# CPU.net
KiCad netlist of a schematic drawn in Altium Designer
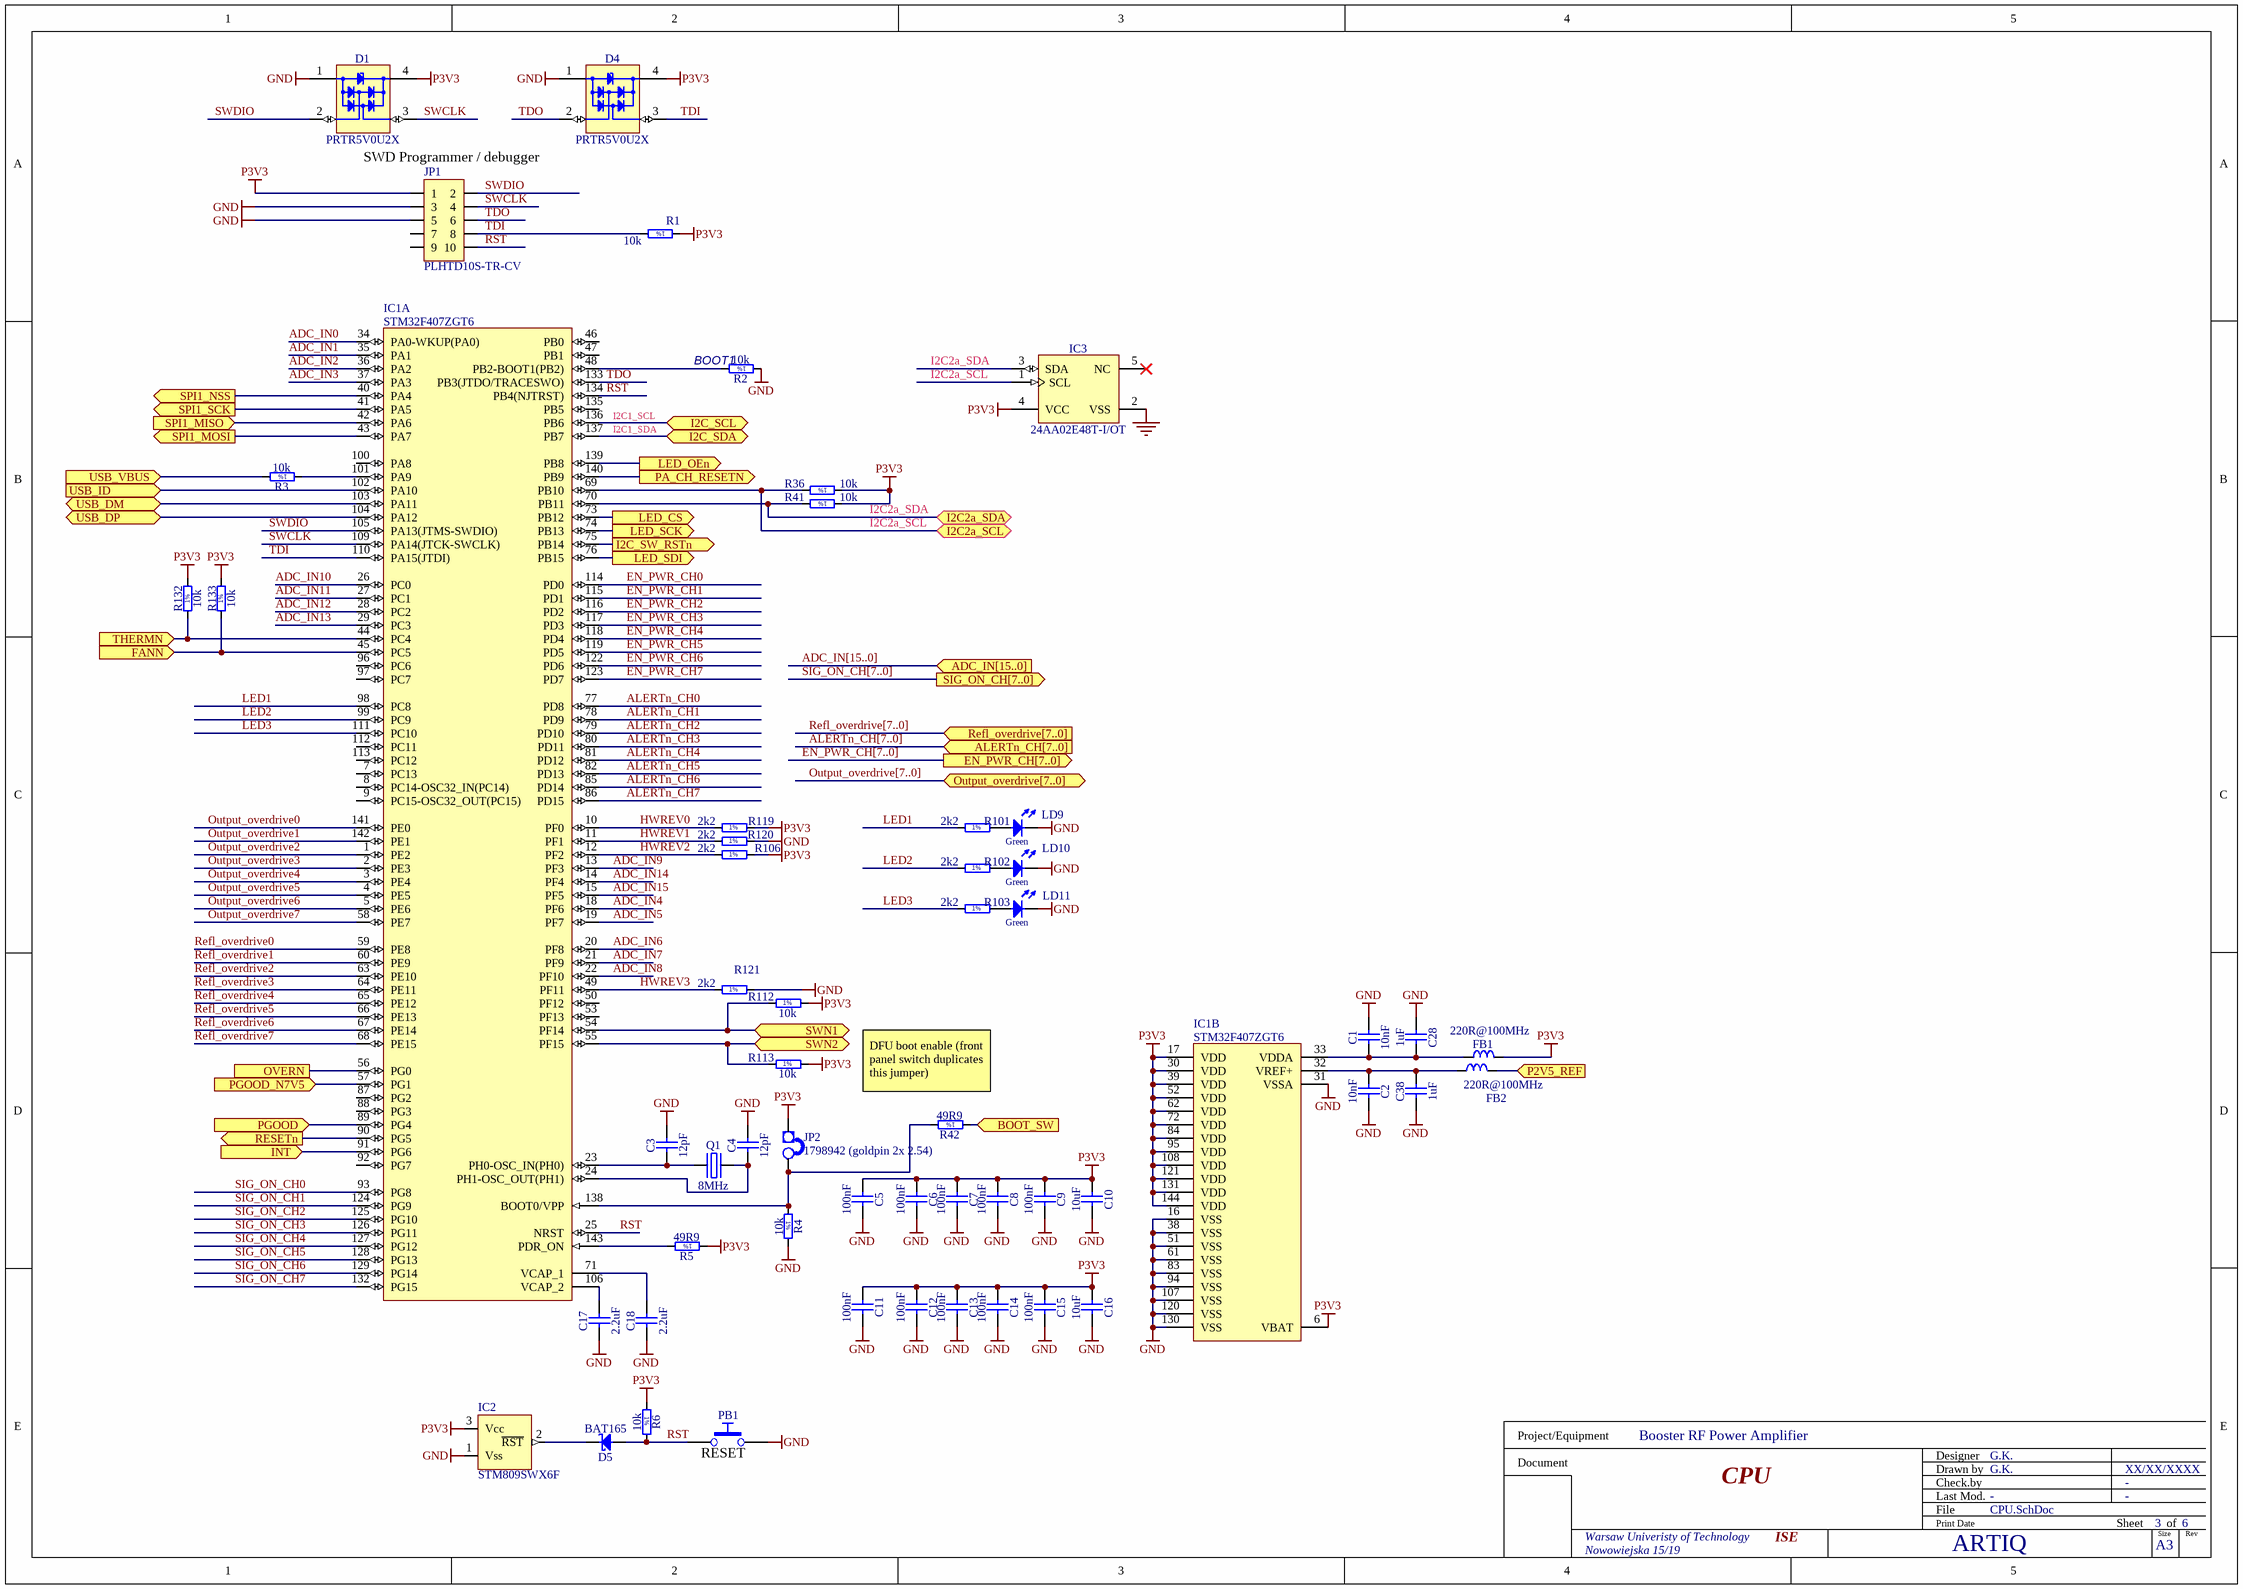
[diagram p0: CPU.SchDoc]

(export (version "E")
  (design (tool "Eeschema 10.0.6"))
  (components
    (comp (ref "C1")
      (value "10nF")
      (footprint "CAPC1005X55N")
      (description "Non-polarised capacitor")
      (fields
        (field (name "PART NUMBER") "CC0402_10NF_16V_10%_X7R")
        (field (name "VOLTAGE") "16V")
        (field (name "AUTHOR") "CERN DEM JLC")
      )
      (libsource (lib "Capacitors") (part "Capacitor - non polarized"))
    )
    (comp (ref "C2")
      (value "10nF")
      (footprint "CAPC1005X55N")
      (description "Non-polarised capacitor")
      (fields
        (field (name "PART NUMBER") "CC0402_10NF_16V_10%_X7R")
        (field (name "VOLTAGE") "16V")
        (field (name "AUTHOR") "CERN DEM JLC")
      )
      (libsource (lib "Capacitors") (part "Capacitor - non polarized"))
    )
    (comp (ref "C3")
      (value "12pF")
      (footprint "CAPC1005X55N")
      (description "Non-polarised capacitor")
      (fields
        (field (name "PART NUMBER") "CC0402_12PF_50V_5%_C0G")
        (field (name "VOLTAGE") "50V")
        (field (name "AUTHOR") "CERN DEM JLC")
      )
      (libsource (lib "Capacitors") (part "Capacitor - non polarized"))
    )
    (comp (ref "C4")
      (value "12pF")
      (footprint "CAPC1005X55N")
      (description "Non-polarised capacitor")
      (fields
        (field (name "PART NUMBER") "CC0402_12PF_50V_5%_C0G")
        (field (name "VOLTAGE") "50V")
        (field (name "AUTHOR") "CERN DEM JLC")
      )
      (libsource (lib "Capacitors") (part "Capacitor - non polarized"))
    )
    (comp (ref "C5")
      (value "100nF")
      (footprint "CAPC1005X55N")
      (description "Non-polarised capacitor")
      (fields
        (field (name "PART NUMBER") "CC0402_100NF_16V_10%_X7R")
        (field (name "VOLTAGE") "16V")
        (field (name "AUTHOR") "CERN DEM JLC")
      )
      (libsource (lib "Capacitors") (part "Capacitor - non polarized"))
    )
    (comp (ref "C6")
      (value "100nF")
      (footprint "CAPC1005X55N")
      (description "Non-polarised capacitor")
      (fields
        (field (name "PART NUMBER") "CC0402_100NF_16V_10%_X7R")
        (field (name "VOLTAGE") "16V")
        (field (name "AUTHOR") "CERN DEM JLC")
      )
      (libsource (lib "Capacitors") (part "Capacitor - non polarized"))
    )
    (comp (ref "C7")
      (value "100nF")
      (footprint "CAPC1005X55N")
      (description "Non-polarised capacitor")
      (fields
        (field (name "PART NUMBER") "CC0402_100NF_16V_10%_X7R")
        (field (name "VOLTAGE") "16V")
        (field (name "AUTHOR") "CERN DEM JLC")
      )
      (libsource (lib "Capacitors") (part "Capacitor - non polarized"))
    )
    (comp (ref "C8")
      (value "100nF")
      (footprint "CAPC1005X55N")
      (description "Non-polarised capacitor")
      (fields
        (field (name "PART NUMBER") "CC0402_100NF_16V_10%_X7R")
        (field (name "VOLTAGE") "16V")
        (field (name "AUTHOR") "CERN DEM JLC")
      )
      (libsource (lib "Capacitors") (part "Capacitor - non polarized"))
    )
    (comp (ref "C9")
      (value "100nF")
      (footprint "CAPC1005X55N")
      (description "Non-polarised capacitor")
      (fields
        (field (name "PART NUMBER") "CC0402_100NF_16V_10%_X7R")
        (field (name "VOLTAGE") "16V")
        (field (name "AUTHOR") "CERN DEM JLC")
      )
      (libsource (lib "Capacitors") (part "Capacitor - non polarized"))
    )
    (comp (ref "C10")
      (value "10uF")
      (footprint "CAPC2012X135N")
      (description "Non-polarised capacitor")
      (fields
        (field (name "PART NUMBER") "CC0805_10UF_16V_10%_X5R")
        (field (name "VOLTAGE") "16V")
        (field (name "AUTHOR") "CERN DEM JLC")
      )
      (libsource (lib "Capacitors") (part "Capacitor - non polarized"))
    )
    (comp (ref "C11")
      (value "100nF")
      (footprint "CAPC1005X55N")
      (description "Non-polarised capacitor")
      (fields
        (field (name "PART NUMBER") "CC0402_100NF_16V_10%_X7R")
        (field (name "VOLTAGE") "16V")
        (field (name "AUTHOR") "CERN DEM JLC")
      )
      (libsource (lib "Capacitors") (part "Capacitor - non polarized"))
    )
    (comp (ref "C12")
      (value "100nF")
      (footprint "CAPC1005X55N")
      (description "Non-polarised capacitor")
      (fields
        (field (name "PART NUMBER") "CC0402_100NF_16V_10%_X7R")
        (field (name "VOLTAGE") "16V")
        (field (name "AUTHOR") "CERN DEM JLC")
      )
      (libsource (lib "Capacitors") (part "Capacitor - non polarized"))
    )
    (comp (ref "C13")
      (value "100nF")
      (footprint "CAPC1005X55N")
      (description "Non-polarised capacitor")
      (fields
        (field (name "PART NUMBER") "CC0402_100NF_16V_10%_X7R")
        (field (name "VOLTAGE") "16V")
        (field (name "AUTHOR") "CERN DEM JLC")
      )
      (libsource (lib "Capacitors") (part "Capacitor - non polarized"))
    )
    (comp (ref "C14")
      (value "100nF")
      (footprint "CAPC1005X55N")
      (description "Non-polarised capacitor")
      (fields
        (field (name "PART NUMBER") "CC0402_100NF_16V_10%_X7R")
        (field (name "VOLTAGE") "16V")
        (field (name "AUTHOR") "CERN DEM JLC")
      )
      (libsource (lib "Capacitors") (part "Capacitor - non polarized"))
    )
    (comp (ref "C15")
      (value "100nF")
      (footprint "CAPC1005X55N")
      (description "Non-polarised capacitor")
      (fields
        (field (name "PART NUMBER") "CC0402_100NF_16V_10%_X7R")
        (field (name "VOLTAGE") "16V")
        (field (name "AUTHOR") "CERN DEM JLC")
      )
      (libsource (lib "Capacitors") (part "Capacitor - non polarized"))
    )
    (comp (ref "C16")
      (value "10uF")
      (footprint "CAPC2012X135N")
      (description "Non-polarised capacitor")
      (fields
        (field (name "PART NUMBER") "CC0805_10UF_16V_10%_X5R")
        (field (name "VOLTAGE") "16V")
        (field (name "AUTHOR") "CERN DEM JLC")
      )
      (libsource (lib "Capacitors") (part "Capacitor - non polarized"))
    )
    (comp (ref "C17")
      (value "2.2uF")
      (footprint "CAPC1608X90N")
      (description "Non-polarised capacitor")
      (fields
        (field (name "PART NUMBER") "CC0603_2.2UF_10V_20%_X7R")
        (field (name "VOLTAGE") "10V")
        (field (name "AUTHOR") "CERN DEM JLC")
      )
      (libsource (lib "Capacitors") (part "Capacitor - non polarized"))
    )
    (comp (ref "C18")
      (value "2.2uF")
      (footprint "CAPC1608X90N")
      (description "Non-polarised capacitor")
      (fields
        (field (name "PART NUMBER") "CC0603_2.2UF_10V_20%_X7R")
        (field (name "VOLTAGE") "10V")
        (field (name "AUTHOR") "CERN DEM JLC")
      )
      (libsource (lib "Capacitors") (part "Capacitor - non polarized"))
    )
    (comp (ref "C28")
      (value "1uF")
      (footprint "CAPC2012X110N")
      (description "Non-polarised capacitor")
      (fields
        (field (name "PART NUMBER") "CC0805_1UF_50V_10%_X7R")
        (field (name "VOLTAGE") "50V")
        (field (name "AUTHOR") "CERN DEM JLC")
      )
      (libsource (lib "Capacitors") (part "Capacitor - non polarized"))
    )
    (comp (ref "C38")
      (value "1uF")
      (footprint "CAPC2012X110N")
      (description "Non-polarised capacitor")
      (fields
        (field (name "PART NUMBER") "CC0805_1UF_50V_10%_X7R")
        (field (name "VOLTAGE") "50V")
        (field (name "AUTHOR") "CERN DEM JLC")
      )
      (libsource (lib "Capacitors") (part "Capacitor - non polarized"))
    )
    (comp (ref "D1")
      (value "PRTR5V0U2X")
      (footprint "SOT190P230X110-4N")
      (description "Ultra Low Capacitance Double Rail-to-Rail ESD Protection Diode")
      (fields
        (field (name "VOLTAGE") "5.5V")
        (field (name "MANUFACTURER") "NXP SEMICONDUCTORS")
        (field (name "AUTHOR") "CERN DEM JLC")
      )
      (libsource (lib "ICs And Semiconductors") (part "PRTR5V0U2X"))
    )
    (comp (ref "D4")
      (value "PRTR5V0U2X")
      (footprint "SOT190P230X110-4N")
      (description "Ultra Low Capacitance Double Rail-to-Rail ESD Protection Diode")
      (fields
        (field (name "VOLTAGE") "5.5V")
        (field (name "MANUFACTURER") "NXP SEMICONDUCTORS")
        (field (name "AUTHOR") "CERN DEM JLC")
      )
      (libsource (lib "ICs And Semiconductors") (part "PRTR5V0U2X"))
    )
    (comp (ref "D5")
      (value "BAT165")
      (footprint "SOD2512X110N")
      (description "Schottky Diode")
      (fields
        (field (name "VOLTAGE") "40V")
        (field (name "POWER") "750mA")
        (field (name "AUTHOR") "CERN DEM JLC")
      )
      (libsource (lib "ICs And Semiconductors") (part "Diode Schottky"))
    )
    (comp (ref "FB1")
      (value "220R@100MHz")
      (footprint "INDC2012X105N")
      (description "Inductor")
      (fields
        (field (name "PART NUMBER") "IND0805_MURATA_BLM21PG221SN1D")
        (field (name "POWER") "2A")
        (field (name "AUTHOR") "CERN DEM JLC")
      )
      (libsource (lib "Inductors & Transformers") (part "Inductor"))
    )
    (comp (ref "FB2")
      (value "220R@100MHz")
      (footprint "INDC2012X105N")
      (description "Inductor")
      (fields
        (field (name "PART NUMBER") "IND0805_MURATA_BLM21PG221SN1D")
        (field (name "POWER") "2A")
        (field (name "AUTHOR") "CERN DEM JLC")
      )
      (libsource (lib "Inductors & Transformers") (part "Inductor"))
    )
    (comp (ref "IC1")
      (value "STM32F407ZGT6")
      (footprint "QFP50P2200X2200X160-144N")
      (fields (field (name "MANUFACTURER") "ST MICROELECTRONICS") (field (name "AUTHOR") "CERN DEM MR"))
      (libsource (lib "ICs And Semiconductors") (part "STM32F407ZGT6"))
    )
    (comp (ref "IC2")
      (value "STM809SWX6F")
      (footprint "SOT-23")
      (description "2.93V  Reset circuit")
      (libsource (lib "LIBRARY_SCH") (part "VMON_STM809"))
    )
    (comp (ref "IC3")
      (value "24AA02E48T-I/OT")
      (footprint "SOT95P280X145-5N")
      (description "1.7V-5.5V, 2K I2C Serial EEPROM With EUI-48 Node Identity")
      (fields (field (name "MANUFACTURER") "MICROCHIP TECHNOLOGY") (field (name "AUTHOR") "CERN DEM MR"))
      (libsource (lib "ICs And Semiconductors") (part "24AA02E48T-I/OT"))
    )
    (comp (ref "JP1")
      (value "PLHTD10S-TR-CV")
      (footprint "PLHTD10S-TR-CV")
      (description "1.27 mm dual row goldpin (Maritex)")
      (libsource (lib "LIBRARY_SCH") (part "CON_2x5 1.27 SMT Male"))
    )
    (comp (ref "JP2")
      (value "1798942 (goldpin 2x 2.54)")
      (footprint "jump")
      (description "Jumper")
      (fields (field (name "MANUFACTURER PART NUMBER") "BG030-02-A-0650-0300-N-G"))
      (libsource (lib "LIBRARY_SCH") (part "JUMPER"))
    )
    (comp (ref "LD9")
      (value "Green")
      (footprint "LED_OSRAM_LGL29K")
      (description "LED Green 1C 2A")
      (fields
        (field (name "PART NUMBER") "LED_OSRAM_LG L29K-G2J1-24-Z")
        (field (name "MANUFACTURER") "OSRAM")
        (field (name "AUTHOR") "CERN DEM JLC")
      )
      (libsource (lib "ICs And Semiconductors") (part "LED Green 1C 2A"))
    )
    (comp (ref "LD10")
      (value "Green")
      (footprint "LED_OSRAM_LGL29K")
      (description "LED Green 1C 2A")
      (fields
        (field (name "PART NUMBER") "LED_OSRAM_LG L29K-G2J1-24-Z")
        (field (name "MANUFACTURER") "OSRAM")
        (field (name "AUTHOR") "CERN DEM JLC")
      )
      (libsource (lib "ICs And Semiconductors") (part "LED Green 1C 2A"))
    )
    (comp (ref "LD11")
      (value "Green")
      (footprint "LED_OSRAM_LGL29K")
      (description "LED Green 1C 2A")
      (fields
        (field (name "PART NUMBER") "LED_OSRAM_LG L29K-G2J1-24-Z")
        (field (name "MANUFACTURER") "OSRAM")
        (field (name "AUTHOR") "CERN DEM JLC")
      )
      (libsource (lib "ICs And Semiconductors") (part "LED Green 1C 2A"))
    )
    (comp (ref "PB1")
      (value "Push Button")
      (footprint "PB_TYCO_FSMSM")
      (description "Push-Button Switch SPDT")
      (fields
        (field (name "PART NUMBER") "PB_TYCO_FSMSM")
        (field (name "MANUFACTURER") "TYCO ELECTRONICS")
        (field (name "AUTHOR") "CERN DEM JLC")
      )
      (libsource (lib "Eletro-mechanical") (part "PB SPST 1NO-2NO"))
    )
    (comp (ref "Q1")
      (value "8MHz")
      (footprint "XTAL_TXC_7A")
      (description "Quartz Crystal")
      (fields
        (field (name "PART NUMBER") "XTAL_8MHZ_TXC_7A-8.000MAAE-T")
        (field (name "MANUFACTURER") "TXC CORPORATION")
        (field (name "AUTHOR") "CERN DEM JLC")
      )
      (libsource (lib "ICs And Semiconductors") (part "Quartz Crystal"))
    )
    (comp (ref "R1")
      (value "10k")
      (footprint "RESC1005X40N")
      (description "Resistor - 1%")
      (fields
        (field (name "PART NUMBER") "R0402_10K_1%_0.0625W_100PPM")
        (field (name "POWER") "0.0625W")
        (field (name "AUTHOR") "CERN DEM JLC")
      )
      (libsource (lib "Resistors") (part "Resistor - 1%"))
    )
    (comp (ref "R2")
      (value "10k")
      (footprint "RESC1005X40N")
      (description "Resistor - 1%")
      (fields
        (field (name "PART NUMBER") "R0402_10K_1%_0.0625W_100PPM")
        (field (name "POWER") "0.0625W")
        (field (name "AUTHOR") "CERN DEM JLC")
      )
      (libsource (lib "Resistors") (part "Resistor - 1%"))
    )
    (comp (ref "R3")
      (value "10k")
      (footprint "RESC1005X40N")
      (description "Resistor - 1%")
      (fields
        (field (name "PART NUMBER") "R0402_10K_1%_0.0625W_100PPM")
        (field (name "POWER") "0.0625W")
        (field (name "AUTHOR") "CERN DEM JLC")
      )
      (libsource (lib "Resistors") (part "Resistor - 1%"))
    )
    (comp (ref "R4")
      (value "10k")
      (footprint "RESC1005X40N")
      (description "Resistor - 1%")
      (fields
        (field (name "PART NUMBER") "R0402_10K_1%_0.0625W_100PPM")
        (field (name "POWER") "0.0625W")
        (field (name "AUTHOR") "CERN DEM JLC")
      )
      (libsource (lib "Resistors") (part "Resistor - 1%"))
    )
    (comp (ref "R5")
      (value "49R9")
      (footprint "RESC1005X40N")
      (description "Resistor - 1%")
      (fields
        (field (name "PART NUMBER") "R0402_49R9_1%_0.0625W_100PPM")
        (field (name "POWER") "0.0625W")
        (field (name "AUTHOR") "CERN DEM JLC")
      )
      (libsource (lib "Resistors") (part "Resistor - 1%"))
    )
    (comp (ref "R6")
      (value "10k")
      (footprint "RESC1005X40N")
      (description "Resistor - 1%")
      (fields
        (field (name "PART NUMBER") "R0402_10K_1%_0.0625W_100PPM")
        (field (name "POWER") "0.0625W")
        (field (name "AUTHOR") "CERN DEM JLC")
      )
      (libsource (lib "Resistors") (part "Resistor - 1%"))
    )
    (comp (ref "R36")
      (value "10k")
      (footprint "RESC1005X40N")
      (description "Resistor - 1%")
      (fields
        (field (name "PART NUMBER") "R0402_10K_1%_0.0625W_100PPM")
        (field (name "POWER") "0.0625W")
        (field (name "AUTHOR") "CERN DEM JLC")
      )
      (libsource (lib "Resistors") (part "Resistor - 1%"))
    )
    (comp (ref "R41")
      (value "10k")
      (footprint "RESC1005X40N")
      (description "Resistor - 1%")
      (fields
        (field (name "PART NUMBER") "R0402_10K_1%_0.0625W_100PPM")
        (field (name "POWER") "0.0625W")
        (field (name "AUTHOR") "CERN DEM JLC")
      )
      (libsource (lib "Resistors") (part "Resistor - 1%"))
    )
    (comp (ref "R42")
      (value "49R9")
      (footprint "RESC1005X40N")
      (description "Resistor - 1%")
      (fields
        (field (name "PART NUMBER") "R0402_49R9_1%_0.0625W_100PPM")
        (field (name "POWER") "0.0625W")
        (field (name "AUTHOR") "CERN DEM JLC")
      )
      (libsource (lib "Resistors") (part "Resistor - 1%"))
    )
    (comp (ref "R101")
      (value "2k2")
      (footprint "RESC1005X40N")
      (description "Resistor - 1%")
      (fields
        (field (name "PART NUMBER") "R0402_2K2_1%_0.0625W_100PPM")
        (field (name "POWER") "0.0625W")
        (field (name "AUTHOR") "CERN DEM JLC")
      )
      (libsource (lib "Resistors") (part "Resistor - 1%"))
    )
    (comp (ref "R102")
      (value "2k2")
      (footprint "RESC1005X40N")
      (description "Resistor - 1%")
      (fields
        (field (name "PART NUMBER") "R0402_2K2_1%_0.0625W_100PPM")
        (field (name "POWER") "0.0625W")
        (field (name "AUTHOR") "CERN DEM JLC")
      )
      (libsource (lib "Resistors") (part "Resistor - 1%"))
    )
    (comp (ref "R103")
      (value "2k2")
      (footprint "RESC1005X40N")
      (description "Resistor - 1%")
      (fields
        (field (name "PART NUMBER") "R0402_2K2_1%_0.0625W_100PPM")
        (field (name "POWER") "0.0625W")
        (field (name "AUTHOR") "CERN DEM JLC")
      )
      (libsource (lib "Resistors") (part "Resistor - 1%"))
    )
    (comp (ref "R106")
      (value "2k2")
      (footprint "RESC1005X40N")
      (description "Resistor - 1%")
      (fields
        (field (name "PART NUMBER") "R0402_2K2_1%_0.0625W_100PPM")
        (field (name "POWER") "0.0625W")
        (field (name "AUTHOR") "CERN DEM JLC")
      )
      (libsource (lib "Resistors") (part "Resistor - 1%"))
    )
    (comp (ref "R112")
      (value "10k")
      (footprint "RESC1005X40N")
      (description "Resistor - 1%")
      (fields
        (field (name "PART NUMBER") "R0402_10K_1%_0.0625W_100PPM")
        (field (name "POWER") "0.0625W")
        (field (name "AUTHOR") "CERN DEM JLC")
      )
      (libsource (lib "Resistors") (part "Resistor - 1%"))
    )
    (comp (ref "R113")
      (value "10k")
      (footprint "RESC1005X40N")
      (description "Resistor - 1%")
      (fields
        (field (name "PART NUMBER") "R0402_10K_1%_0.0625W_100PPM")
        (field (name "POWER") "0.0625W")
        (field (name "AUTHOR") "CERN DEM JLC")
      )
      (libsource (lib "Resistors") (part "Resistor - 1%"))
    )
    (comp (ref "R119")
      (value "2k2")
      (footprint "RESC1005X40N")
      (description "Resistor - 1%")
      (fields
        (field (name "PART NUMBER") "R0402_2K2_1%_0.0625W_100PPM")
        (field (name "POWER") "0.0625W")
        (field (name "AUTHOR") "CERN DEM JLC")
      )
      (libsource (lib "Resistors") (part "Resistor - 1%"))
    )
    (comp (ref "R120")
      (value "2k2")
      (footprint "RESC1005X40N")
      (description "Resistor - 1%")
      (fields
        (field (name "PART NUMBER") "R0402_2K2_1%_0.0625W_100PPM")
        (field (name "POWER") "0.0625W")
        (field (name "AUTHOR") "CERN DEM JLC")
      )
      (libsource (lib "Resistors") (part "Resistor - 1%"))
    )
    (comp (ref "R121")
      (value "2k2")
      (footprint "RESC1005X40N")
      (description "Resistor - 1%")
      (fields
        (field (name "PART NUMBER") "R0402_2K2_1%_0.0625W_100PPM")
        (field (name "POWER") "0.0625W")
        (field (name "AUTHOR") "CERN DEM JLC")
      )
      (libsource (lib "Resistors") (part "Resistor - 1%"))
    )
    (comp (ref "R132")
      (value "10k")
      (footprint "RESC1005X40N")
      (description "Resistor - 1%")
      (fields
        (field (name "PART NUMBER") "R0402_10K_1%_0.0625W_100PPM")
        (field (name "POWER") "0.0625W")
        (field (name "AUTHOR") "CERN DEM JLC")
      )
      (libsource (lib "Resistors") (part "Resistor - 1%"))
    )
    (comp (ref "R133")
      (value "10k")
      (footprint "RESC1005X40N")
      (description "Resistor - 1%")
      (fields
        (field (name "PART NUMBER") "R0402_10K_1%_0.0625W_100PPM")
        (field (name "POWER") "0.0625W")
        (field (name "AUTHOR") "CERN DEM JLC")
      )
      (libsource (lib "Resistors") (part "Resistor - 1%"))
    )
  )
  (nets
    (net (code "1") (name "/ADC_IN0") (class "Default")
      (node (ref "IC1") (pin "34") (pinfunction "PA0-WKUP(PA0)_34") (pintype "bidirectional"))
    )
    (net (code "2") (name "/ADC_IN1") (class "Default")
      (node (ref "IC1") (pin "35") (pinfunction "PA1_35") (pintype "bidirectional"))
    )
    (net (code "3") (name "/ADC_IN2") (class "Default")
      (node (ref "IC1") (pin "36") (pinfunction "PA2_36") (pintype "bidirectional"))
    )
    (net (code "4") (name "/ADC_IN3") (class "Default")
      (node (ref "IC1") (pin "37") (pinfunction "PA3_37") (pintype "bidirectional"))
    )
    (net (code "5") (name "/ADC_IN4") (class "Default")
      (node (ref "IC1") (pin "18") (pinfunction "PF6_18") (pintype "bidirectional"))
    )
    (net (code "6") (name "/ADC_IN5") (class "Default")
      (node (ref "IC1") (pin "19") (pinfunction "PF7_19") (pintype "bidirectional"))
    )
    (net (code "7") (name "/ADC_IN6") (class "Default")
      (node (ref "IC1") (pin "20") (pinfunction "PF8_20") (pintype "bidirectional"))
    )
    (net (code "8") (name "/ADC_IN7") (class "Default")
      (node (ref "IC1") (pin "21") (pinfunction "PF9_21") (pintype "bidirectional"))
    )
    (net (code "9") (name "/ADC_IN8") (class "Default")
      (node (ref "IC1") (pin "22") (pinfunction "PF10_22") (pintype "bidirectional"))
    )
    (net (code "10") (name "/ADC_IN9") (class "Default")
      (node (ref "IC1") (pin "13") (pinfunction "PF3_13") (pintype "bidirectional"))
    )
    (net (code "11") (name "/ADC_IN10") (class "Default")
      (node (ref "IC1") (pin "26") (pinfunction "PC0_26") (pintype "bidirectional"))
    )
    (net (code "12") (name "/ADC_IN11") (class "Default")
      (node (ref "IC1") (pin "27") (pinfunction "PC1_27") (pintype "bidirectional"))
    )
    (net (code "13") (name "/ADC_IN12") (class "Default")
      (node (ref "IC1") (pin "28") (pinfunction "PC2_28") (pintype "bidirectional"))
    )
    (net (code "14") (name "/ADC_IN13") (class "Default")
      (node (ref "IC1") (pin "29") (pinfunction "PC3_29") (pintype "bidirectional"))
    )
    (net (code "15") (name "/ADC_IN14") (class "Default")
      (node (ref "IC1") (pin "14") (pinfunction "PF4_14") (pintype "bidirectional"))
    )
    (net (code "16") (name "/ADC_IN15") (class "Default")
      (node (ref "IC1") (pin "15") (pinfunction "PF5_15") (pintype "bidirectional"))
    )
    (net (code "18") (name "/ALERTn_CH0") (class "Default")
      (node (ref "IC1") (pin "77") (pinfunction "PD8_77") (pintype "bidirectional"))
    )
    (net (code "19") (name "/ALERTn_CH1") (class "Default")
      (node (ref "IC1") (pin "78") (pinfunction "PD9_78") (pintype "bidirectional"))
    )
    (net (code "20") (name "/ALERTn_CH2") (class "Default")
      (node (ref "IC1") (pin "79") (pinfunction "PD10_79") (pintype "bidirectional"))
    )
    (net (code "21") (name "/ALERTn_CH3") (class "Default")
      (node (ref "IC1") (pin "80") (pinfunction "PD11_80") (pintype "bidirectional"))
    )
    (net (code "22") (name "/ALERTn_CH4") (class "Default")
      (node (ref "IC1") (pin "81") (pinfunction "PD12_81") (pintype "bidirectional"))
    )
    (net (code "23") (name "/ALERTn_CH5") (class "Default")
      (node (ref "IC1") (pin "82") (pinfunction "PD13_82") (pintype "bidirectional"))
    )
    (net (code "24") (name "/ALERTn_CH6") (class "Default")
      (node (ref "IC1") (pin "85") (pinfunction "PD14_85") (pintype "bidirectional"))
    )
    (net (code "25") (name "/ALERTn_CH7") (class "Default")
      (node (ref "IC1") (pin "86") (pinfunction "PD15_86") (pintype "bidirectional"))
    )
    (net (code "27") (name "/BOOT_SW") (class "Default")
      (node (ref "R42") (pin "1") (pinfunction "1_1") (pintype "passive"))
    )
    (net (code "28") (name "/EN_PWR_CH0") (class "Default")
      (node (ref "IC1") (pin "114") (pinfunction "PD0_114") (pintype "bidirectional"))
    )
    (net (code "29") (name "/EN_PWR_CH1") (class "Default")
      (node (ref "IC1") (pin "115") (pinfunction "PD1_115") (pintype "bidirectional"))
    )
    (net (code "30") (name "/EN_PWR_CH2") (class "Default")
      (node (ref "IC1") (pin "116") (pinfunction "PD2_116") (pintype "bidirectional"))
    )
    (net (code "31") (name "/EN_PWR_CH3") (class "Default")
      (node (ref "IC1") (pin "117") (pinfunction "PD3_117") (pintype "bidirectional"))
    )
    (net (code "32") (name "/EN_PWR_CH4") (class "Default")
      (node (ref "IC1") (pin "118") (pinfunction "PD4_118") (pintype "bidirectional"))
    )
    (net (code "33") (name "/EN_PWR_CH5") (class "Default")
      (node (ref "IC1") (pin "119") (pinfunction "PD5_119") (pintype "bidirectional"))
    )
    (net (code "34") (name "/EN_PWR_CH6") (class "Default")
      (node (ref "IC1") (pin "122") (pinfunction "PD6_122") (pintype "bidirectional"))
    )
    (net (code "35") (name "/EN_PWR_CH7") (class "Default")
      (node (ref "IC1") (pin "123") (pinfunction "PD7_123") (pintype "bidirectional"))
    )
    (net (code "37") (name "/FANN") (class "Default")
      (node (ref "IC1") (pin "45") (pinfunction "PC5_45") (pintype "bidirectional"))
      (node (ref "R133") (pin "1") (pinfunction "1_1") (pintype "passive"))
    )
    (net (code "38") (name "/HWREV0") (class "Default")
      (node (ref "IC1") (pin "10") (pinfunction "PF0_10") (pintype "bidirectional"))
      (node (ref "R119") (pin "1") (pinfunction "1_1") (pintype "passive"))
    )
    (net (code "39") (name "/HWREV1") (class "Default")
      (node (ref "IC1") (pin "11") (pinfunction "PF1_11") (pintype "bidirectional"))
      (node (ref "R120") (pin "1") (pinfunction "1_1") (pintype "passive"))
    )
    (net (code "40") (name "/HWREV2") (class "Default")
      (node (ref "IC1") (pin "12") (pinfunction "PF2_12") (pintype "bidirectional"))
      (node (ref "R106") (pin "1") (pinfunction "1_1") (pintype "passive"))
    )
    (net (code "41") (name "/HWREV3") (class "Default")
      (node (ref "IC1") (pin "49") (pinfunction "PF11_49") (pintype "bidirectional"))
      (node (ref "R121") (pin "1") (pinfunction "1_1") (pintype "passive"))
    )
    (net (code "42") (name "/I2C2a_SCL") (class "Default")
      (node (ref "IC1") (pin "69") (pinfunction "PB10_69") (pintype "bidirectional"))
      (node (ref "IC3") (pin "1") (pinfunction "SCL_1") (pintype "input"))
      (node (ref "R36") (pin "2") (pinfunction "2_2") (pintype "passive"))
    )
    (net (code "43") (name "/I2C2a_SDA") (class "Default")
      (node (ref "IC1") (pin "70") (pinfunction "PB11_70") (pintype "bidirectional"))
      (node (ref "IC3") (pin "3") (pinfunction "SDA_3") (pintype "bidirectional"))
      (node (ref "R41") (pin "2") (pinfunction "2_2") (pintype "passive"))
    )
    (net (code "44") (name "/I2C_SCL") (class "Default")
      (node (ref "IC1") (pin "136") (pinfunction "PB6_136") (pintype "bidirectional"))
    )
    (net (code "45") (name "/I2C_SDA") (class "Default")
      (node (ref "IC1") (pin "137") (pinfunction "PB7_137") (pintype "bidirectional"))
    )
    (net (code "46") (name "/I2C_SW_RSTn") (class "Default")
      (node (ref "IC1") (pin "75") (pinfunction "PB14_75") (pintype "bidirectional"))
    )
    (net (code "47") (name "/INT") (class "Default")
      (node (ref "IC1") (pin "91") (pinfunction "PG6_91") (pintype "bidirectional"))
    )
    (net (code "48") (name "/LED1") (class "Default")
      (node (ref "IC1") (pin "98") (pinfunction "PC8_98") (pintype "bidirectional"))
      (node (ref "R101") (pin "1") (pinfunction "1_1") (pintype "passive"))
    )
    (net (code "49") (name "/LED2") (class "Default")
      (node (ref "IC1") (pin "99") (pinfunction "PC9_99") (pintype "bidirectional"))
      (node (ref "R102") (pin "1") (pinfunction "1_1") (pintype "passive"))
    )
    (net (code "50") (name "/LED3") (class "Default")
      (node (ref "IC1") (pin "111") (pinfunction "PC10_111") (pintype "bidirectional"))
      (node (ref "R103") (pin "1") (pinfunction "1_1") (pintype "passive"))
    )
    (net (code "51") (name "/LED_CS") (class "Default")
      (node (ref "IC1") (pin "73") (pinfunction "PB12_73") (pintype "bidirectional"))
    )
    (net (code "52") (name "/LED_OEn") (class "Default")
      (node (ref "IC1") (pin "139") (pinfunction "PB8_139") (pintype "bidirectional"))
    )
    (net (code "53") (name "/LED_SCK") (class "Default")
      (node (ref "IC1") (pin "74") (pinfunction "PB13_74") (pintype "bidirectional"))
    )
    (net (code "54") (name "/LED_SDI") (class "Default")
      (node (ref "IC1") (pin "76") (pinfunction "PB15_76") (pintype "bidirectional"))
    )
    (net (code "55") (name "/OVERN") (class "Default")
      (node (ref "IC1") (pin "56") (pinfunction "PG0_56") (pintype "bidirectional"))
    )
    (net (code "56") (name "/Output_overdrive0") (class "Default")
      (node (ref "IC1") (pin "141") (pinfunction "PE0_141") (pintype "bidirectional"))
    )
    (net (code "57") (name "/Output_overdrive1") (class "Default")
      (node (ref "IC1") (pin "142") (pinfunction "PE1_142") (pintype "bidirectional"))
    )
    (net (code "58") (name "/Output_overdrive2") (class "Default")
      (node (ref "IC1") (pin "1") (pinfunction "PE2_1") (pintype "bidirectional"))
    )
    (net (code "59") (name "/Output_overdrive3") (class "Default")
      (node (ref "IC1") (pin "2") (pinfunction "PE3_2") (pintype "bidirectional"))
    )
    (net (code "60") (name "/Output_overdrive4") (class "Default")
      (node (ref "IC1") (pin "3") (pinfunction "PE4_3") (pintype "bidirectional"))
    )
    (net (code "61") (name "/Output_overdrive5") (class "Default")
      (node (ref "IC1") (pin "4") (pinfunction "PE5_4") (pintype "bidirectional"))
    )
    (net (code "62") (name "/Output_overdrive6") (class "Default")
      (node (ref "IC1") (pin "5") (pinfunction "PE6_5") (pintype "bidirectional"))
    )
    (net (code "63") (name "/Output_overdrive7") (class "Default")
      (node (ref "IC1") (pin "58") (pinfunction "PE7_58") (pintype "bidirectional"))
    )
    (net (code "65") (name "/P2V5_REF") (class "Default")
      (node (ref "FB2") (pin "2") (pinfunction "2_2") (pintype "passive"))
    )
    (net (code "66") (name "/PA_CH_RESETN") (class "Default")
      (node (ref "IC1") (pin "140") (pinfunction "PB9_140") (pintype "bidirectional"))
    )
    (net (code "67") (name "/PGOOD") (class "Default")
      (node (ref "IC1") (pin "89") (pinfunction "PG4_89") (pintype "bidirectional"))
    )
    (net (code "68") (name "/PGOOD_N7V5") (class "Default")
      (node (ref "IC1") (pin "57") (pinfunction "PG1_57") (pintype "bidirectional"))
    )
    (net (code "69") (name "/RESETn") (class "Default")
      (node (ref "IC1") (pin "90") (pinfunction "PG5_90") (pintype "bidirectional"))
    )
    (net (code "70") (name "/RST") (class "Default")
      (node (ref "D5") (pin "2") (pinfunction "A_2") (pintype "passive"))
      (node (ref "IC1") (pin "134") (pinfunction "PB4(NJTRST)_134") (pintype "bidirectional"))
      (node (ref "IC1") (pin "25") (pinfunction "NRST_25") (pintype "bidirectional"))
      (node (ref "JP1") (pin "10") (pinfunction "10_10") (pintype "passive"))
      (node (ref "PB1") (pin "1") (pinfunction "1_1") (pintype "passive"))
      (node (ref "R6") (pin "2") (pinfunction "2_2") (pintype "passive"))
    )
    (net (code "71") (name "/Refl_overdrive0") (class "Default")
      (node (ref "IC1") (pin "59") (pinfunction "PE8_59") (pintype "bidirectional"))
    )
    (net (code "72") (name "/Refl_overdrive1") (class "Default")
      (node (ref "IC1") (pin "60") (pinfunction "PE9_60") (pintype "bidirectional"))
    )
    (net (code "73") (name "/Refl_overdrive2") (class "Default")
      (node (ref "IC1") (pin "63") (pinfunction "PE10_63") (pintype "bidirectional"))
    )
    (net (code "74") (name "/Refl_overdrive3") (class "Default")
      (node (ref "IC1") (pin "64") (pinfunction "PE11_64") (pintype "bidirectional"))
    )
    (net (code "75") (name "/Refl_overdrive4") (class "Default")
      (node (ref "IC1") (pin "65") (pinfunction "PE12_65") (pintype "bidirectional"))
    )
    (net (code "76") (name "/Refl_overdrive5") (class "Default")
      (node (ref "IC1") (pin "66") (pinfunction "PE13_66") (pintype "bidirectional"))
    )
    (net (code "77") (name "/Refl_overdrive6") (class "Default")
      (node (ref "IC1") (pin "67") (pinfunction "PE14_67") (pintype "bidirectional"))
    )
    (net (code "78") (name "/Refl_overdrive7") (class "Default")
      (node (ref "IC1") (pin "68") (pinfunction "PE15_68") (pintype "bidirectional"))
    )
    (net (code "80") (name "/SIG_ON_CH0") (class "Default")
      (node (ref "IC1") (pin "93") (pinfunction "PG8_93") (pintype "bidirectional"))
    )
    (net (code "81") (name "/SIG_ON_CH1") (class "Default")
      (node (ref "IC1") (pin "124") (pinfunction "PG9_124") (pintype "bidirectional"))
    )
    (net (code "82") (name "/SIG_ON_CH2") (class "Default")
      (node (ref "IC1") (pin "125") (pinfunction "PG10_125") (pintype "bidirectional"))
    )
    (net (code "83") (name "/SIG_ON_CH3") (class "Default")
      (node (ref "IC1") (pin "126") (pinfunction "PG11_126") (pintype "bidirectional"))
    )
    (net (code "84") (name "/SIG_ON_CH4") (class "Default")
      (node (ref "IC1") (pin "127") (pinfunction "PG12_127") (pintype "bidirectional"))
    )
    (net (code "85") (name "/SIG_ON_CH5") (class "Default")
      (node (ref "IC1") (pin "128") (pinfunction "PG13_128") (pintype "bidirectional"))
    )
    (net (code "86") (name "/SIG_ON_CH6") (class "Default")
      (node (ref "IC1") (pin "129") (pinfunction "PG14_129") (pintype "bidirectional"))
    )
    (net (code "87") (name "/SIG_ON_CH7") (class "Default")
      (node (ref "IC1") (pin "132") (pinfunction "PG15_132") (pintype "bidirectional"))
    )
    (net (code "89") (name "/SPI1_MISO") (class "Default")
      (node (ref "IC1") (pin "42") (pinfunction "PA6_42") (pintype "bidirectional"))
    )
    (net (code "90") (name "/SPI1_MOSI") (class "Default")
      (node (ref "IC1") (pin "43") (pinfunction "PA7_43") (pintype "bidirectional"))
    )
    (net (code "91") (name "/SPI1_NSS") (class "Default")
      (node (ref "IC1") (pin "40") (pinfunction "PA4_40") (pintype "bidirectional"))
    )
    (net (code "92") (name "/SPI1_SCK") (class "Default")
      (node (ref "IC1") (pin "41") (pinfunction "PA5_41") (pintype "bidirectional"))
    )
    (net (code "93") (name "/SWCLK") (class "Default")
      (node (ref "D1") (pin "3") (pinfunction "I/O2_3") (pintype "bidirectional"))
      (node (ref "IC1") (pin "109") (pinfunction "PA14(JTCK-SWCLK)_109") (pintype "bidirectional"))
      (node (ref "JP1") (pin "4") (pinfunction "4_4") (pintype "passive"))
    )
    (net (code "94") (name "/SWDIO") (class "Default")
      (node (ref "D1") (pin "2") (pinfunction "I/O1_2") (pintype "bidirectional"))
      (node (ref "IC1") (pin "105") (pinfunction "PA13(JTMS-SWDIO)_105") (pintype "bidirectional"))
      (node (ref "JP1") (pin "2") (pinfunction "2_2") (pintype "passive"))
    )
    (net (code "95") (name "/SWN1") (class "Default")
      (node (ref "IC1") (pin "54") (pinfunction "PF14_54") (pintype "bidirectional"))
      (node (ref "R112") (pin "1") (pinfunction "1_1") (pintype "passive"))
    )
    (net (code "96") (name "/SWN2") (class "Default")
      (node (ref "IC1") (pin "55") (pinfunction "PF15_55") (pintype "bidirectional"))
      (node (ref "R113") (pin "1") (pinfunction "1_1") (pintype "passive"))
    )
    (net (code "97") (name "/TDI") (class "Default")
      (node (ref "D4") (pin "3") (pinfunction "I/O2_3") (pintype "bidirectional"))
      (node (ref "IC1") (pin "110") (pinfunction "PA15(JTDI)_110") (pintype "bidirectional"))
      (node (ref "JP1") (pin "8") (pinfunction "8_8") (pintype "passive"))
      (node (ref "R1") (pin "2") (pinfunction "2_2") (pintype "passive"))
    )
    (net (code "98") (name "/TDO") (class "Default")
      (node (ref "D4") (pin "2") (pinfunction "I/O1_2") (pintype "bidirectional"))
      (node (ref "IC1") (pin "133") (pinfunction "PB3(JTDO/TRACESWO)_133") (pintype "bidirectional"))
      (node (ref "JP1") (pin "6") (pinfunction "6_6") (pintype "passive"))
    )
    (net (code "99") (name "/THERMN") (class "Default")
      (node (ref "IC1") (pin "44") (pinfunction "PC4_44") (pintype "bidirectional"))
      (node (ref "R132") (pin "1") (pinfunction "1_1") (pintype "passive"))
    )
    (net (code "100") (name "/USB_DM") (class "Default")
      (node (ref "IC1") (pin "103") (pinfunction "PA11_103") (pintype "bidirectional"))
    )
    (net (code "101") (name "/USB_DP") (class "Default")
      (node (ref "IC1") (pin "104") (pinfunction "PA12_104") (pintype "bidirectional"))
    )
    (net (code "102") (name "/USB_ID") (class "Default")
      (node (ref "IC1") (pin "102") (pinfunction "PA10_102") (pintype "bidirectional"))
    )
    (net (code "103") (name "/USB_VBUS") (class "Default")
      (node (ref "R3") (pin "2") (pinfunction "2_2") (pintype "passive"))
    )
    (net (code "104") (name "GND") (class "Default")
      (node (ref "C1") (pin "2") (pinfunction "2_2") (pintype "passive"))
      (node (ref "C10") (pin "2") (pinfunction "2_2") (pintype "passive"))
      (node (ref "C11") (pin "2") (pinfunction "2_2") (pintype "passive"))
      (node (ref "C12") (pin "2") (pinfunction "2_2") (pintype "passive"))
      (node (ref "C13") (pin "2") (pinfunction "2_2") (pintype "passive"))
      (node (ref "C14") (pin "2") (pinfunction "2_2") (pintype "passive"))
      (node (ref "C15") (pin "2") (pinfunction "2_2") (pintype "passive"))
      (node (ref "C16") (pin "2") (pinfunction "2_2") (pintype "passive"))
      (node (ref "C17") (pin "1") (pinfunction "1_1") (pintype "passive"))
      (node (ref "C18") (pin "1") (pinfunction "1_1") (pintype "passive"))
      (node (ref "C2") (pin "2") (pinfunction "2_2") (pintype "passive"))
      (node (ref "C28") (pin "1") (pinfunction "1_1") (pintype "passive"))
      (node (ref "C3") (pin "2") (pinfunction "2_2") (pintype "passive"))
      (node (ref "C38") (pin "1") (pinfunction "1_1") (pintype "passive"))
      (node (ref "C4") (pin "2") (pinfunction "2_2") (pintype "passive"))
      (node (ref "C5") (pin "2") (pinfunction "2_2") (pintype "passive"))
      (node (ref "C6") (pin "2") (pinfunction "2_2") (pintype "passive"))
      (node (ref "C7") (pin "2") (pinfunction "2_2") (pintype "passive"))
      (node (ref "C8") (pin "2") (pinfunction "2_2") (pintype "passive"))
      (node (ref "C9") (pin "2") (pinfunction "2_2") (pintype "passive"))
      (node (ref "D1") (pin "1") (pinfunction "GND_1") (pintype "power_in"))
      (node (ref "D4") (pin "1") (pinfunction "GND_1") (pintype "power_in"))
      (node (ref "IC1") (pin "107") (pinfunction "VSS_107") (pintype "power_in"))
      (node (ref "IC1") (pin "120") (pinfunction "VSS_120") (pintype "power_in"))
      (node (ref "IC1") (pin "130") (pinfunction "VSS_130") (pintype "power_in"))
      (node (ref "IC1") (pin "16") (pinfunction "VSS_16") (pintype "power_in"))
      (node (ref "IC1") (pin "31") (pinfunction "VSSA_31") (pintype "power_in"))
      (node (ref "IC1") (pin "38") (pinfunction "VSS_38") (pintype "power_in"))
      (node (ref "IC1") (pin "51") (pinfunction "VSS_51") (pintype "power_in"))
      (node (ref "IC1") (pin "61") (pinfunction "VSS_61") (pintype "power_in"))
      (node (ref "IC1") (pin "83") (pinfunction "VSS_83") (pintype "power_in"))
      (node (ref "IC1") (pin "94") (pinfunction "VSS_94") (pintype "power_in"))
      (node (ref "IC2") (pin "1") (pinfunction "Vss_1") (pintype "power_in"))
      (node (ref "IC3") (pin "2") (pinfunction "VSS_2") (pintype "power_in"))
      (node (ref "JP1") (pin "3") (pinfunction "3_3") (pintype "passive"))
      (node (ref "JP1") (pin "5") (pinfunction "5_5") (pintype "passive"))
      (node (ref "LD10") (pin "1") (pinfunction "C_1") (pintype "passive"))
      (node (ref "LD11") (pin "1") (pinfunction "C_1") (pintype "passive"))
      (node (ref "LD9") (pin "1") (pinfunction "C_1") (pintype "passive"))
      (node (ref "PB1") (pin "2") (pinfunction "2_2") (pintype "passive"))
      (node (ref "R120") (pin "2") (pinfunction "2_2") (pintype "passive"))
      (node (ref "R121") (pin "2") (pinfunction "2_2") (pintype "passive"))
      (node (ref "R2") (pin "1") (pinfunction "1_1") (pintype "passive"))
      (node (ref "R4") (pin "2") (pinfunction "2_2") (pintype "passive"))
    )
    (net (code "105") (name "Net-(D5-C)") (class "Default")
      (node (ref "D5") (pin "1") (pinfunction "C_1") (pintype "passive"))
      (node (ref "IC2") (pin "2") (pinfunction "~{RST}_2") (pintype "output"))
    )
    (net (code "106") (name "Net-(IC1A-BOOT0{slash}VPP)") (class "Default")
      (node (ref "IC1") (pin "138") (pinfunction "BOOT0/VPP_138") (pintype "input"))
      (node (ref "JP2") (pin "2") (pinfunction "E2_2") (pintype "passive"))
      (node (ref "R4") (pin "1") (pinfunction "1_1") (pintype "passive"))
      (node (ref "R42") (pin "2") (pinfunction "2_2") (pintype "passive"))
    )
    (net (code "107") (name "Net-(IC1A-PA9)") (class "Default")
      (node (ref "IC1") (pin "101") (pinfunction "PA9_101") (pintype "bidirectional"))
      (node (ref "R3") (pin "1") (pinfunction "1_1") (pintype "passive"))
    )
    (net (code "108") (name "Net-(IC1A-PB2-BOOT1(PB2))") (class "Default")
      (node (ref "IC1") (pin "48") (pinfunction "PB2-BOOT1(PB2)_48") (pintype "bidirectional"))
      (node (ref "R2") (pin "2") (pinfunction "2_2") (pintype "passive"))
    )
    (net (code "109") (name "Net-(IC1A-PDR_ON)") (class "Default")
      (node (ref "IC1") (pin "143") (pinfunction "PDR_ON_143") (pintype "input"))
      (node (ref "R5") (pin "2") (pinfunction "2_2") (pintype "passive"))
    )
    (net (code "110") (name "Net-(IC1A-PH0-OSC_IN(PH0))") (class "Default")
      (node (ref "C3") (pin "1") (pinfunction "1_1") (pintype "passive"))
      (node (ref "IC1") (pin "23") (pinfunction "PH0-OSC_IN(PH0)_23") (pintype "bidirectional"))
      (node (ref "Q1") (pin "1") (pinfunction "OSC1_1") (pintype "passive"))
    )
    (net (code "111") (name "Net-(IC1A-PH1-OSC_OUT(PH1))") (class "Default")
      (node (ref "C4") (pin "1") (pinfunction "1_1") (pintype "passive"))
      (node (ref "IC1") (pin "24") (pinfunction "PH1-OSC_OUT(PH1)_24") (pintype "bidirectional"))
      (node (ref "Q1") (pin "2") (pinfunction "OSC2_2") (pintype "passive"))
    )
    (net (code "112") (name "Net-(IC1A-VCAP_1)") (class "Default")
      (node (ref "C18") (pin "2") (pinfunction "2_2") (pintype "passive"))
      (node (ref "IC1") (pin "71") (pinfunction "VCAP_1_71") (pintype "power_in"))
    )
    (net (code "113") (name "Net-(IC1A-VCAP_2)") (class "Default")
      (node (ref "C17") (pin "2") (pinfunction "2_2") (pintype "passive"))
      (node (ref "IC1") (pin "106") (pinfunction "VCAP_2_106") (pintype "power_in"))
    )
    (net (code "114") (name "Net-(IC1B-VDDA)") (class "Default")
      (node (ref "C1") (pin "1") (pinfunction "1_1") (pintype "passive"))
      (node (ref "C28") (pin "2") (pinfunction "2_2") (pintype "passive"))
      (node (ref "FB1") (pin "1") (pinfunction "1_1") (pintype "passive"))
      (node (ref "IC1") (pin "33") (pinfunction "VDDA_33") (pintype "power_in"))
    )
    (net (code "115") (name "Net-(IC1B-VREF+)") (class "Default")
      (node (ref "C2") (pin "1") (pinfunction "1_1") (pintype "passive"))
      (node (ref "C38") (pin "2") (pinfunction "2_2") (pintype "passive"))
      (node (ref "FB2") (pin "1") (pinfunction "1_1") (pintype "passive"))
      (node (ref "IC1") (pin "32") (pinfunction "VREF+_32") (pintype "power_in"))
    )
    (net (code "116") (name "Net-(LD9-A)") (class "Default")
      (node (ref "LD9") (pin "2") (pinfunction "A_2") (pintype "passive"))
      (node (ref "R101") (pin "2") (pinfunction "2_2") (pintype "passive"))
    )
    (net (code "117") (name "Net-(LD10-A)") (class "Default")
      (node (ref "LD10") (pin "2") (pinfunction "A_2") (pintype "passive"))
      (node (ref "R102") (pin "2") (pinfunction "2_2") (pintype "passive"))
    )
    (net (code "118") (name "Net-(LD11-A)") (class "Default")
      (node (ref "LD11") (pin "2") (pinfunction "A_2") (pintype "passive"))
      (node (ref "R103") (pin "2") (pinfunction "2_2") (pintype "passive"))
    )
    (net (code "119") (name "P3V3") (class "Default")
      (node (ref "C10") (pin "1") (pinfunction "1_1") (pintype "passive"))
      (node (ref "C11") (pin "1") (pinfunction "1_1") (pintype "passive"))
      (node (ref "C12") (pin "1") (pinfunction "1_1") (pintype "passive"))
      (node (ref "C13") (pin "1") (pinfunction "1_1") (pintype "passive"))
      (node (ref "C14") (pin "1") (pinfunction "1_1") (pintype "passive"))
      (node (ref "C15") (pin "1") (pinfunction "1_1") (pintype "passive"))
      (node (ref "C16") (pin "1") (pinfunction "1_1") (pintype "passive"))
      (node (ref "C5") (pin "1") (pinfunction "1_1") (pintype "passive"))
      (node (ref "C6") (pin "1") (pinfunction "1_1") (pintype "passive"))
      (node (ref "C7") (pin "1") (pinfunction "1_1") (pintype "passive"))
      (node (ref "C8") (pin "1") (pinfunction "1_1") (pintype "passive"))
      (node (ref "C9") (pin "1") (pinfunction "1_1") (pintype "passive"))
      (node (ref "D1") (pin "4") (pinfunction "VCC_4") (pintype "power_in"))
      (node (ref "D4") (pin "4") (pinfunction "VCC_4") (pintype "power_in"))
      (node (ref "FB1") (pin "2") (pinfunction "2_2") (pintype "passive"))
      (node (ref "IC1") (pin "108") (pinfunction "VDD_108") (pintype "power_in"))
      (node (ref "IC1") (pin "121") (pinfunction "VDD_121") (pintype "power_in"))
      (node (ref "IC1") (pin "131") (pinfunction "VDD_131") (pintype "power_in"))
      (node (ref "IC1") (pin "144") (pinfunction "VDD_144") (pintype "power_in"))
      (node (ref "IC1") (pin "17") (pinfunction "VDD_17") (pintype "power_in"))
      (node (ref "IC1") (pin "30") (pinfunction "VDD_30") (pintype "power_in"))
      (node (ref "IC1") (pin "39") (pinfunction "VDD_39") (pintype "power_in"))
      (node (ref "IC1") (pin "52") (pinfunction "VDD_52") (pintype "power_in"))
      (node (ref "IC1") (pin "6") (pinfunction "VBAT_6") (pintype "power_in"))
      (node (ref "IC1") (pin "62") (pinfunction "VDD_62") (pintype "power_in"))
      (node (ref "IC1") (pin "72") (pinfunction "VDD_72") (pintype "power_in"))
      (node (ref "IC1") (pin "84") (pinfunction "VDD_84") (pintype "power_in"))
      (node (ref "IC1") (pin "95") (pinfunction "VDD_95") (pintype "power_in"))
      (node (ref "IC2") (pin "3") (pinfunction "Vcc_3") (pintype "power_in"))
      (node (ref "IC3") (pin "4") (pinfunction "VCC_4") (pintype "power_in"))
      (node (ref "JP1") (pin "1") (pinfunction "1_1") (pintype "passive"))
      (node (ref "JP2") (pin "1") (pinfunction "E1_1") (pintype "passive"))
      (node (ref "R1") (pin "1") (pinfunction "1_1") (pintype "passive"))
      (node (ref "R106") (pin "2") (pinfunction "2_2") (pintype "passive"))
      (node (ref "R112") (pin "2") (pinfunction "2_2") (pintype "passive"))
      (node (ref "R113") (pin "2") (pinfunction "2_2") (pintype "passive"))
      (node (ref "R119") (pin "2") (pinfunction "2_2") (pintype "passive"))
      (node (ref "R132") (pin "2") (pinfunction "2_2") (pintype "passive"))
      (node (ref "R133") (pin "2") (pinfunction "2_2") (pintype "passive"))
      (node (ref "R36") (pin "1") (pinfunction "1_1") (pintype "passive"))
      (node (ref "R41") (pin "1") (pinfunction "1_1") (pintype "passive"))
      (node (ref "R5") (pin "1") (pinfunction "1_1") (pintype "passive"))
      (node (ref "R6") (pin "1") (pinfunction "1_1") (pintype "passive"))
    )
    (net (code "120") (name "unconnected-(IC1A-PA8-Pad100)") (class "Default")
      (node (ref "IC1") (pin "100") (pinfunction "PA8_100") (pintype "bidirectional"))
    )
    (net (code "121") (name "unconnected-(IC1A-PB0-Pad46)") (class "Default")
      (node (ref "IC1") (pin "46") (pinfunction "PB0_46") (pintype "bidirectional"))
    )
    (net (code "122") (name "unconnected-(IC1A-PB1-Pad47)") (class "Default")
      (node (ref "IC1") (pin "47") (pinfunction "PB1_47") (pintype "bidirectional"))
    )
    (net (code "123") (name "unconnected-(IC1A-PB5-Pad135)") (class "Default")
      (node (ref "IC1") (pin "135") (pinfunction "PB5_135") (pintype "bidirectional"))
    )
    (net (code "124") (name "unconnected-(IC1A-PC6-Pad96)") (class "Default")
      (node (ref "IC1") (pin "96") (pinfunction "PC6_96") (pintype "bidirectional"))
    )
    (net (code "125") (name "unconnected-(IC1A-PC7-Pad97)") (class "Default")
      (node (ref "IC1") (pin "97") (pinfunction "PC7_97") (pintype "bidirectional"))
    )
    (net (code "126") (name "unconnected-(IC1A-PC11-Pad112)") (class "Default")
      (node (ref "IC1") (pin "112") (pinfunction "PC11_112") (pintype "bidirectional"))
    )
    (net (code "127") (name "unconnected-(IC1A-PC12-Pad113)") (class "Default")
      (node (ref "IC1") (pin "113") (pinfunction "PC12_113") (pintype "bidirectional"))
    )
    (net (code "128") (name "unconnected-(IC1A-PC13-Pad7)") (class "Default")
      (node (ref "IC1") (pin "7") (pinfunction "PC13_7") (pintype "bidirectional"))
    )
    (net (code "129") (name "unconnected-(IC1A-PC14-OSC32_IN(PC14)-Pad8)") (class "Default")
      (node (ref "IC1") (pin "8") (pinfunction "PC14-OSC32_IN(PC14)_8") (pintype "bidirectional"))
    )
    (net (code "130") (name "unconnected-(IC1A-PC15-OSC32_OUT(PC15)-Pad9)") (class "Default")
      (node (ref "IC1") (pin "9") (pinfunction "PC15-OSC32_OUT(PC15)_9") (pintype "bidirectional"))
    )
    (net (code "131") (name "unconnected-(IC1A-PF12-Pad50)") (class "Default")
      (node (ref "IC1") (pin "50") (pinfunction "PF12_50") (pintype "bidirectional"))
    )
    (net (code "132") (name "unconnected-(IC1A-PF13-Pad53)") (class "Default")
      (node (ref "IC1") (pin "53") (pinfunction "PF13_53") (pintype "bidirectional"))
    )
    (net (code "133") (name "unconnected-(IC1A-PG2-Pad87)") (class "Default")
      (node (ref "IC1") (pin "87") (pinfunction "PG2_87") (pintype "bidirectional"))
    )
    (net (code "134") (name "unconnected-(IC1A-PG3-Pad88)") (class "Default")
      (node (ref "IC1") (pin "88") (pinfunction "PG3_88") (pintype "bidirectional"))
    )
    (net (code "135") (name "unconnected-(IC1A-PG7-Pad92)") (class "Default")
      (node (ref "IC1") (pin "92") (pinfunction "PG7_92") (pintype "bidirectional"))
    )
    (net (code "136") (name "unconnected-(IC3-NC-Pad5)") (class "Default")
      (node (ref "IC3") (pin "5") (pinfunction "NC_5") (pintype "passive+no_connect"))
    )
    (net (code "137") (name "unconnected-(JP1-Pad7)") (class "Default")
      (node (ref "JP1") (pin "7") (pinfunction "7_7") (pintype "passive"))
    )
    (net (code "138") (name "unconnected-(JP1-Pad9)") (class "Default")
      (node (ref "JP1") (pin "9") (pinfunction "9_9") (pintype "passive"))
    )
  )
)
